# UFC-PCB.net
KiCad netlist of a schematic drawn in Altium Designer
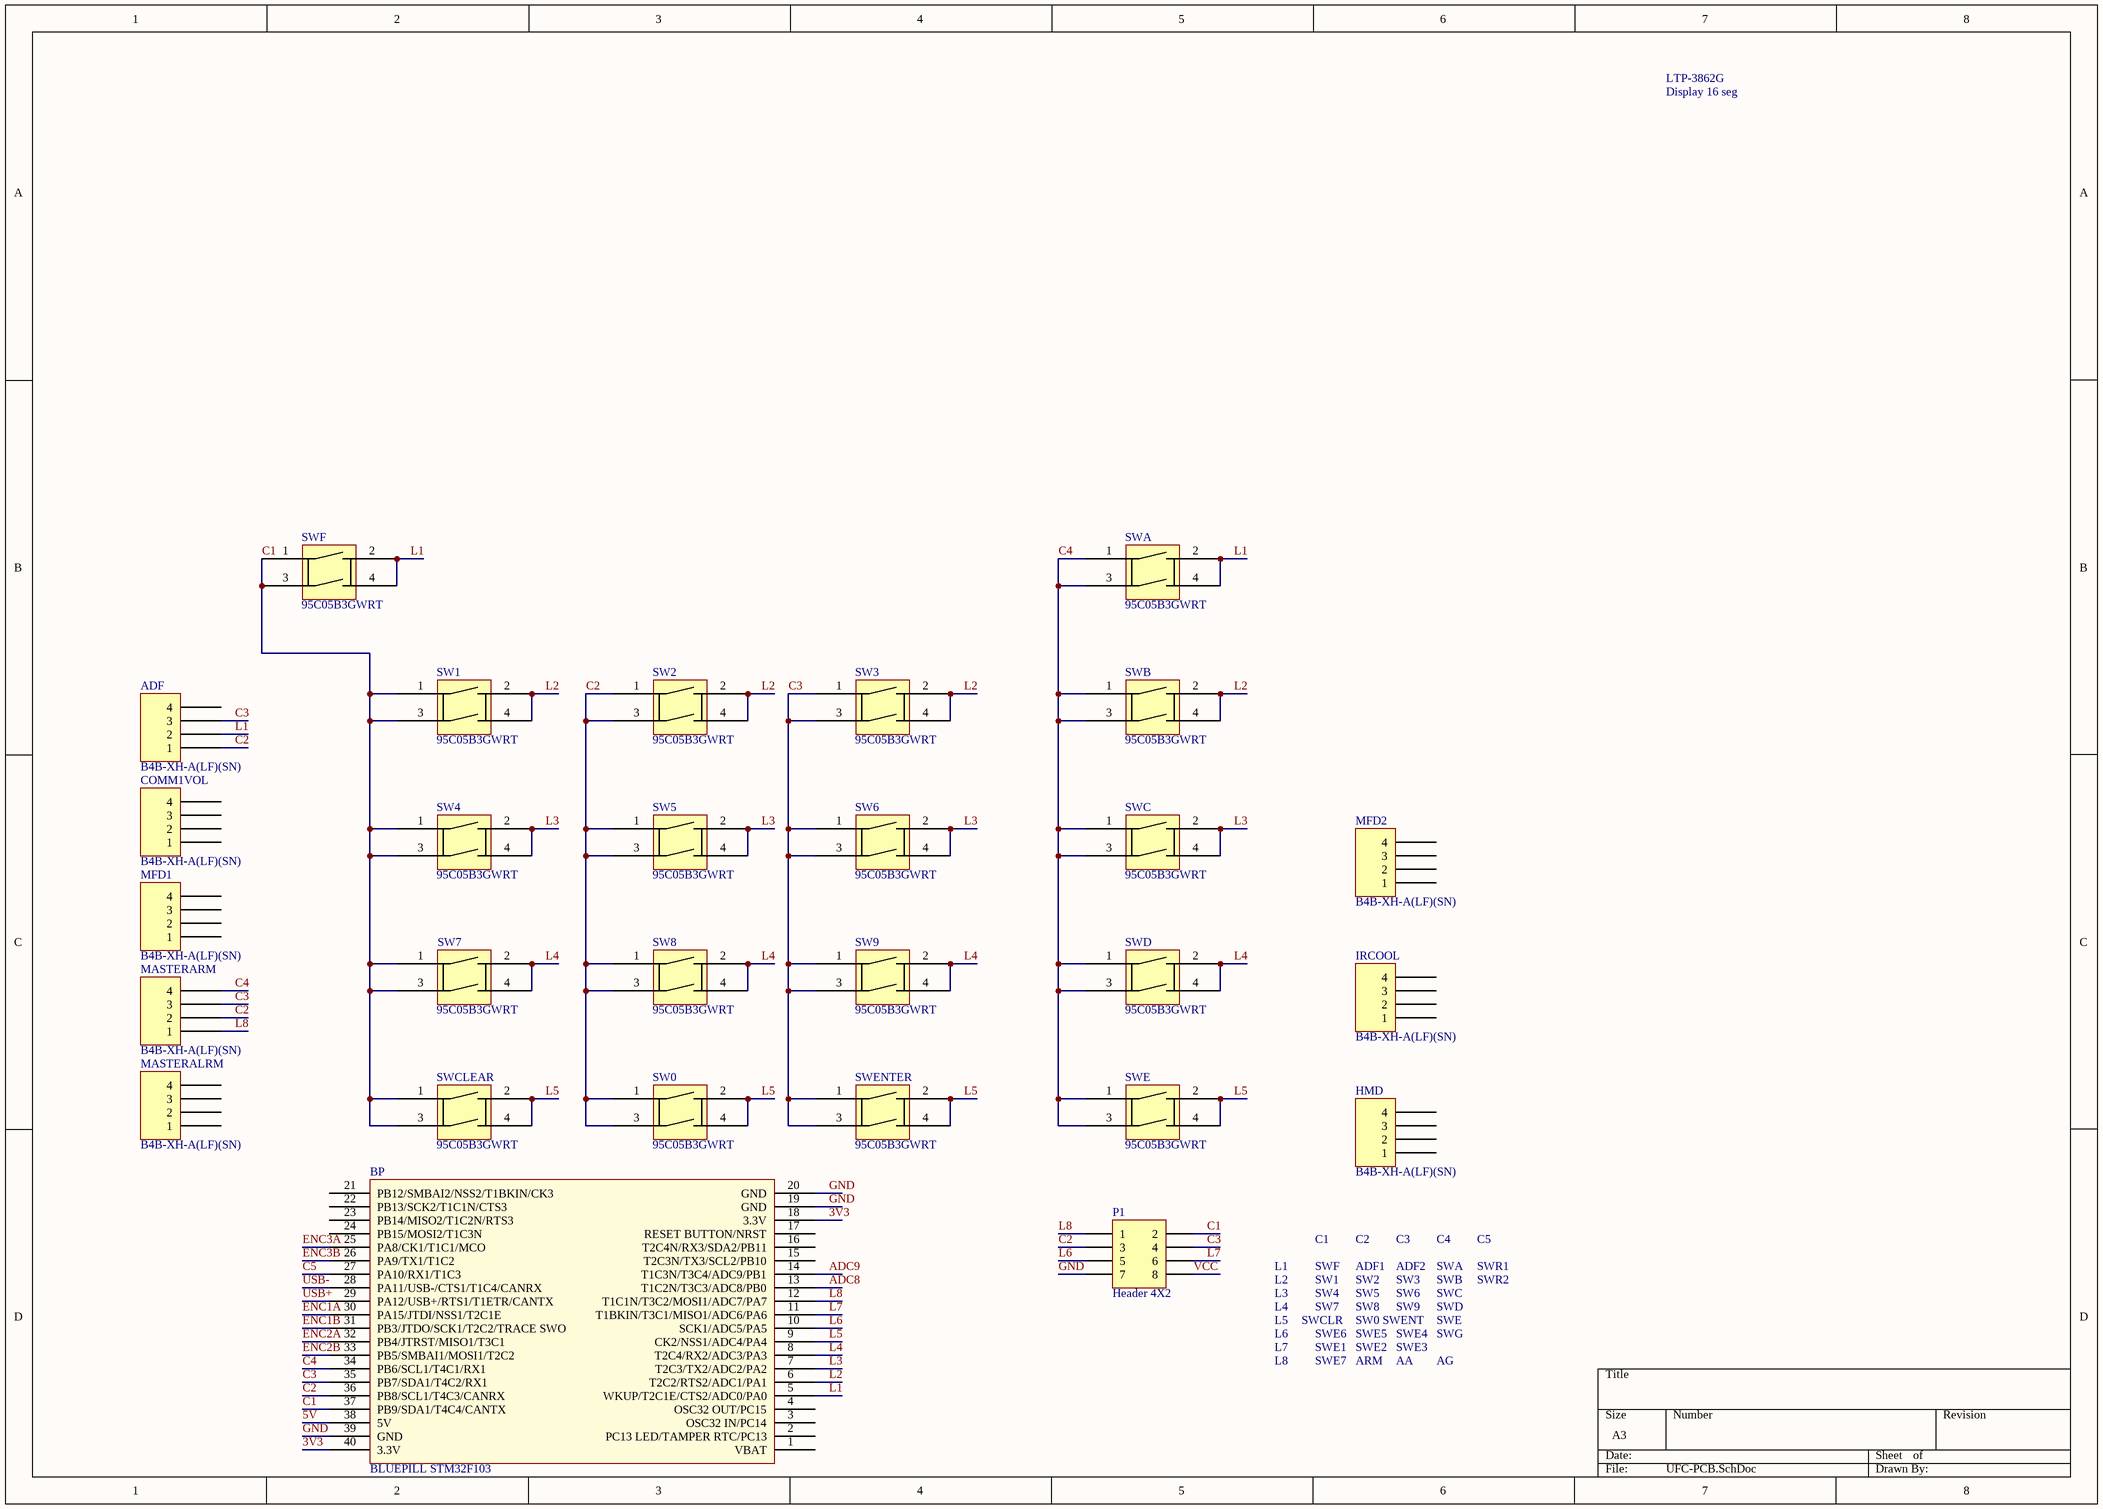
[diagram p0: UFC-PCB.SchDoc]

(export (version "E")
  (design (tool "Eeschema 10.0.6"))
  (components
    (comp (ref "ADF")
      (value "B4B-XH-A(LF)(SN)")
      (footprint "New footprint 1")
      (libsource (lib "IMBEL") (part "4POS CON"))
    )
    (comp (ref "BP")
      (value "BLUEPILL STM32F103")
      (footprint "BLUEPILL-PCB")
      (description "STM32 Blue Pill Development Module")
      (libsource (lib "IMBEL") (part "BLUEPILL-SCH"))
    )
    (comp (ref "COMM1VOL")
      (value "B4B-XH-A(LF)(SN)")
      (footprint "New footprint 1")
      (libsource (lib "IMBEL") (part "4POS CON"))
    )
    (comp (ref "HMD")
      (value "B4B-XH-A(LF)(SN)")
      (footprint "New footprint 1")
      (libsource (lib "IMBEL") (part "4POS CON"))
    )
    (comp (ref "IRCOOL")
      (value "B4B-XH-A(LF)(SN)")
      (footprint "New footprint 1")
      (libsource (lib "IMBEL") (part "4POS CON"))
    )
    (comp (ref "MASTERALRM")
      (value "B4B-XH-A(LF)(SN)")
      (footprint "New footprint 1")
      (libsource (lib "IMBEL") (part "4POS CON"))
    )
    (comp (ref "MASTERARM")
      (value "B4B-XH-A(LF)(SN)")
      (footprint "New footprint 1")
      (libsource (lib "IMBEL") (part "4POS CON"))
    )
    (comp (ref "MFD1")
      (value "B4B-XH-A(LF)(SN)")
      (footprint "New footprint 1")
      (libsource (lib "IMBEL") (part "4POS CON"))
    )
    (comp (ref "MFD2")
      (value "B4B-XH-A(LF)(SN)")
      (footprint "New footprint 1")
      (libsource (lib "IMBEL") (part "4POS CON"))
    )
    (comp (ref "P1")
      (value "Header 4X2")
      (footprint "HDR2X4")
      (description "Header, 4-Pin, Dual row")
      (fields (field (name "PUBLISHER") "Altium Limited"))
      (libsource (lib "Miscellaneous Connectors") (part "Header 4X2"))
    )
    (comp (ref "SW0")
      (value "95C05B3GWRT")
      (footprint "TACTILE-SWITCH-4P")
      (description "SWITCH TACTILE SPST-NO 0.05A 12V")
      (libsource (lib "IMBEL") (part "SWITCH-4P"))
    )
    (comp (ref "SW1")
      (value "95C05B3GWRT")
      (footprint "TACTILE-SWITCH-4P")
      (description "SWITCH TACTILE SPST-NO 0.05A 12V")
      (libsource (lib "IMBEL") (part "SWITCH-4P"))
    )
    (comp (ref "SW2")
      (value "95C05B3GWRT")
      (footprint "TACTILE-SWITCH-4P")
      (description "SWITCH TACTILE SPST-NO 0.05A 12V")
      (libsource (lib "IMBEL") (part "SWITCH-4P"))
    )
    (comp (ref "SW3")
      (value "95C05B3GWRT")
      (footprint "TACTILE-SWITCH-4P")
      (description "SWITCH TACTILE SPST-NO 0.05A 12V")
      (libsource (lib "IMBEL") (part "SWITCH-4P"))
    )
    (comp (ref "SW4")
      (value "95C05B3GWRT")
      (footprint "TACTILE-SWITCH-4P")
      (description "SWITCH TACTILE SPST-NO 0.05A 12V")
      (libsource (lib "IMBEL") (part "SWITCH-4P"))
    )
    (comp (ref "SW5")
      (value "95C05B3GWRT")
      (footprint "TACTILE-SWITCH-4P")
      (description "SWITCH TACTILE SPST-NO 0.05A 12V")
      (libsource (lib "IMBEL") (part "SWITCH-4P"))
    )
    (comp (ref "SW6")
      (value "95C05B3GWRT")
      (footprint "TACTILE-SWITCH-4P")
      (description "SWITCH TACTILE SPST-NO 0.05A 12V")
      (libsource (lib "IMBEL") (part "SWITCH-4P"))
    )
    (comp (ref "SW7")
      (value "95C05B3GWRT")
      (footprint "TACTILE-SWITCH-4P")
      (description "SWITCH TACTILE SPST-NO 0.05A 12V")
      (libsource (lib "IMBEL") (part "SWITCH-4P"))
    )
    (comp (ref "SW8")
      (value "95C05B3GWRT")
      (footprint "TACTILE-SWITCH-4P")
      (description "SWITCH TACTILE SPST-NO 0.05A 12V")
      (libsource (lib "IMBEL") (part "SWITCH-4P"))
    )
    (comp (ref "SW9")
      (value "95C05B3GWRT")
      (footprint "TACTILE-SWITCH-4P")
      (description "SWITCH TACTILE SPST-NO 0.05A 12V")
      (libsource (lib "IMBEL") (part "SWITCH-4P"))
    )
    (comp (ref "SWA")
      (value "95C05B3GWRT")
      (footprint "TACTILE-SWITCH-4P")
      (description "SWITCH TACTILE SPST-NO 0.05A 12V")
      (libsource (lib "IMBEL") (part "SWITCH-4P"))
    )
    (comp (ref "SWB")
      (value "95C05B3GWRT")
      (footprint "TACTILE-SWITCH-4P")
      (description "SWITCH TACTILE SPST-NO 0.05A 12V")
      (libsource (lib "IMBEL") (part "SWITCH-4P"))
    )
    (comp (ref "SWC")
      (value "95C05B3GWRT")
      (footprint "TACTILE-SWITCH-4P")
      (description "SWITCH TACTILE SPST-NO 0.05A 12V")
      (libsource (lib "IMBEL") (part "SWITCH-4P"))
    )
    (comp (ref "SWCLEAR")
      (value "95C05B3GWRT")
      (footprint "TACTILE-SWITCH-4P")
      (description "SWITCH TACTILE SPST-NO 0.05A 12V")
      (libsource (lib "IMBEL") (part "SWITCH-4P"))
    )
    (comp (ref "SWD")
      (value "95C05B3GWRT")
      (footprint "TACTILE-SWITCH-4P")
      (description "SWITCH TACTILE SPST-NO 0.05A 12V")
      (libsource (lib "IMBEL") (part "SWITCH-4P"))
    )
    (comp (ref "SWE")
      (value "95C05B3GWRT")
      (footprint "TACTILE-SWITCH-4P")
      (description "SWITCH TACTILE SPST-NO 0.05A 12V")
      (libsource (lib "IMBEL") (part "SWITCH-4P"))
    )
    (comp (ref "SWENTER")
      (value "95C05B3GWRT")
      (footprint "TACTILE-SWITCH-4P")
      (description "SWITCH TACTILE SPST-NO 0.05A 12V")
      (libsource (lib "IMBEL") (part "SWITCH-4P"))
    )
    (comp (ref "SWF")
      (value "95C05B3GWRT")
      (footprint "TACTILE-SWITCH-4P")
      (description "SWITCH TACTILE SPST-NO 0.05A 12V")
      (libsource (lib "IMBEL") (part "SWITCH-4P"))
    )
  )
  (nets
    (net (code "1") (name "/3V3") (class "Default")
      (node (ref "BP") (pin "18") (pinfunction "3.3V_18") (pintype "passive"))
      (node (ref "BP") (pin "40") (pinfunction "3.3V_40") (pintype "passive"))
    )
    (net (code "2") (name "/5V") (class "Default")
      (node (ref "BP") (pin "38") (pinfunction "5V_38") (pintype "passive"))
    )
    (net (code "3") (name "/ADC8") (class "Default")
      (node (ref "BP") (pin "13") (pinfunction "T1C2N/T3C3/ADC8/PB0_13") (pintype "passive"))
    )
    (net (code "4") (name "/ADC9") (class "Default")
      (node (ref "BP") (pin "14") (pinfunction "T1C3N/T3C4/ADC9/PB1_14") (pintype "passive"))
    )
    (net (code "5") (name "/C1") (class "Default")
      (node (ref "BP") (pin "37") (pinfunction "PB9/SDA1/T4C4/CANTX_37") (pintype "passive"))
      (node (ref "P1") (pin "2") (pinfunction "2_2") (pintype "passive"))
      (node (ref "SW1") (pin "1") (pinfunction "1_1") (pintype "passive"))
      (node (ref "SW1") (pin "3") (pinfunction "3_3") (pintype "passive"))
      (node (ref "SW4") (pin "1") (pinfunction "1_1") (pintype "passive"))
      (node (ref "SW4") (pin "3") (pinfunction "3_3") (pintype "passive"))
      (node (ref "SW7") (pin "1") (pinfunction "1_1") (pintype "passive"))
      (node (ref "SW7") (pin "3") (pinfunction "3_3") (pintype "passive"))
      (node (ref "SWCLEAR") (pin "1") (pinfunction "1_1") (pintype "passive"))
      (node (ref "SWCLEAR") (pin "3") (pinfunction "3_3") (pintype "passive"))
      (node (ref "SWF") (pin "1") (pinfunction "1_1") (pintype "passive"))
      (node (ref "SWF") (pin "3") (pinfunction "3_3") (pintype "passive"))
    )
    (net (code "6") (name "/C2") (class "Default")
      (node (ref "ADF") (pin "1") (pinfunction "1_1") (pintype "open_collector"))
      (node (ref "BP") (pin "36") (pinfunction "PB8/SCL1/T4C3/CANRX_36") (pintype "passive"))
      (node (ref "MASTERARM") (pin "2") (pinfunction "2_2") (pintype "open_collector"))
      (node (ref "P1") (pin "3") (pinfunction "3_3") (pintype "passive"))
      (node (ref "SW0") (pin "1") (pinfunction "1_1") (pintype "passive"))
      (node (ref "SW0") (pin "3") (pinfunction "3_3") (pintype "passive"))
      (node (ref "SW2") (pin "1") (pinfunction "1_1") (pintype "passive"))
      (node (ref "SW2") (pin "3") (pinfunction "3_3") (pintype "passive"))
      (node (ref "SW5") (pin "1") (pinfunction "1_1") (pintype "passive"))
      (node (ref "SW5") (pin "3") (pinfunction "3_3") (pintype "passive"))
      (node (ref "SW8") (pin "1") (pinfunction "1_1") (pintype "passive"))
      (node (ref "SW8") (pin "3") (pinfunction "3_3") (pintype "passive"))
    )
    (net (code "7") (name "/C3") (class "Default")
      (node (ref "ADF") (pin "3") (pinfunction "3_3") (pintype "open_collector"))
      (node (ref "BP") (pin "35") (pinfunction "PB7/SDA1/T4C2/RX1_35") (pintype "passive"))
      (node (ref "MASTERARM") (pin "3") (pinfunction "3_3") (pintype "open_collector"))
      (node (ref "P1") (pin "4") (pinfunction "4_4") (pintype "passive"))
      (node (ref "SW3") (pin "1") (pinfunction "1_1") (pintype "passive"))
      (node (ref "SW3") (pin "3") (pinfunction "3_3") (pintype "passive"))
      (node (ref "SW6") (pin "1") (pinfunction "1_1") (pintype "passive"))
      (node (ref "SW6") (pin "3") (pinfunction "3_3") (pintype "passive"))
      (node (ref "SW9") (pin "1") (pinfunction "1_1") (pintype "passive"))
      (node (ref "SW9") (pin "3") (pinfunction "3_3") (pintype "passive"))
      (node (ref "SWENTER") (pin "1") (pinfunction "1_1") (pintype "passive"))
      (node (ref "SWENTER") (pin "3") (pinfunction "3_3") (pintype "passive"))
    )
    (net (code "8") (name "/C4") (class "Default")
      (node (ref "BP") (pin "34") (pinfunction "PB6/SCL1/T4C1/RX1_34") (pintype "passive"))
      (node (ref "MASTERARM") (pin "4") (pinfunction "4_4") (pintype "open_collector"))
      (node (ref "SWA") (pin "1") (pinfunction "1_1") (pintype "passive"))
      (node (ref "SWA") (pin "3") (pinfunction "3_3") (pintype "passive"))
      (node (ref "SWB") (pin "1") (pinfunction "1_1") (pintype "passive"))
      (node (ref "SWB") (pin "3") (pinfunction "3_3") (pintype "passive"))
      (node (ref "SWC") (pin "1") (pinfunction "1_1") (pintype "passive"))
      (node (ref "SWC") (pin "3") (pinfunction "3_3") (pintype "passive"))
      (node (ref "SWD") (pin "1") (pinfunction "1_1") (pintype "passive"))
      (node (ref "SWD") (pin "3") (pinfunction "3_3") (pintype "passive"))
      (node (ref "SWE") (pin "1") (pinfunction "1_1") (pintype "passive"))
      (node (ref "SWE") (pin "3") (pinfunction "3_3") (pintype "passive"))
    )
    (net (code "9") (name "/C5") (class "Default")
      (node (ref "BP") (pin "27") (pinfunction "PA10/RX1/T1C3_27") (pintype "passive"))
    )
    (net (code "10") (name "/ENC1A") (class "Default")
      (node (ref "BP") (pin "30") (pinfunction "PA15/JTDI/NSS1/T2C1E_30") (pintype "passive"))
    )
    (net (code "11") (name "/ENC1B") (class "Default")
      (node (ref "BP") (pin "31") (pinfunction "PB3/JTDO/SCK1/T2C2/TRACE_SWO_31") (pintype "passive"))
    )
    (net (code "12") (name "/ENC2A") (class "Default")
      (node (ref "BP") (pin "32") (pinfunction "PB4/JTRST/MISO1/T3C1_32") (pintype "passive"))
    )
    (net (code "13") (name "/ENC2B") (class "Default")
      (node (ref "BP") (pin "33") (pinfunction "PB5/SMBAI1/MOSI1/T2C2_33") (pintype "passive"))
    )
    (net (code "14") (name "/ENC3A") (class "Default")
      (node (ref "BP") (pin "25") (pinfunction "PA8/CK1/T1C1/MCO_25") (pintype "passive"))
    )
    (net (code "15") (name "/ENC3B") (class "Default")
      (node (ref "BP") (pin "26") (pinfunction "PA9/TX1/T1C2_26") (pintype "passive"))
    )
    (net (code "16") (name "/GND") (class "Default")
      (node (ref "BP") (pin "19") (pinfunction "GND_19") (pintype "passive"))
      (node (ref "BP") (pin "20") (pinfunction "GND_20") (pintype "passive"))
      (node (ref "BP") (pin "39") (pinfunction "GND_39") (pintype "passive"))
      (node (ref "P1") (pin "7") (pinfunction "7_7") (pintype "passive"))
    )
    (net (code "17") (name "/L1") (class "Default")
      (node (ref "ADF") (pin "2") (pinfunction "2_2") (pintype "open_collector"))
      (node (ref "BP") (pin "5") (pinfunction "WKUP/T2C1E/CTS2/ADC0/PA0_5") (pintype "passive"))
      (node (ref "SWA") (pin "2") (pinfunction "2_2") (pintype "passive"))
      (node (ref "SWA") (pin "4") (pinfunction "4_4") (pintype "passive"))
      (node (ref "SWF") (pin "2") (pinfunction "2_2") (pintype "passive"))
      (node (ref "SWF") (pin "4") (pinfunction "4_4") (pintype "passive"))
    )
    (net (code "18") (name "/L2") (class "Default")
      (node (ref "BP") (pin "6") (pinfunction "T2C2/RTS2/ADC1/PA1_6") (pintype "passive"))
      (node (ref "SW1") (pin "2") (pinfunction "2_2") (pintype "passive"))
      (node (ref "SW1") (pin "4") (pinfunction "4_4") (pintype "passive"))
      (node (ref "SW2") (pin "2") (pinfunction "2_2") (pintype "passive"))
      (node (ref "SW2") (pin "4") (pinfunction "4_4") (pintype "passive"))
      (node (ref "SW3") (pin "2") (pinfunction "2_2") (pintype "passive"))
      (node (ref "SW3") (pin "4") (pinfunction "4_4") (pintype "passive"))
      (node (ref "SWB") (pin "2") (pinfunction "2_2") (pintype "passive"))
      (node (ref "SWB") (pin "4") (pinfunction "4_4") (pintype "passive"))
    )
    (net (code "19") (name "/L3") (class "Default")
      (node (ref "BP") (pin "7") (pinfunction "T2C3/TX2/ADC2/PA2_7") (pintype "passive"))
      (node (ref "SW4") (pin "2") (pinfunction "2_2") (pintype "passive"))
      (node (ref "SW4") (pin "4") (pinfunction "4_4") (pintype "passive"))
      (node (ref "SW5") (pin "2") (pinfunction "2_2") (pintype "passive"))
      (node (ref "SW5") (pin "4") (pinfunction "4_4") (pintype "passive"))
      (node (ref "SW6") (pin "2") (pinfunction "2_2") (pintype "passive"))
      (node (ref "SW6") (pin "4") (pinfunction "4_4") (pintype "passive"))
      (node (ref "SWC") (pin "2") (pinfunction "2_2") (pintype "passive"))
      (node (ref "SWC") (pin "4") (pinfunction "4_4") (pintype "passive"))
    )
    (net (code "20") (name "/L4") (class "Default")
      (node (ref "BP") (pin "8") (pinfunction "T2C4/RX2/ADC3/PA3_8") (pintype "passive"))
      (node (ref "SW7") (pin "2") (pinfunction "2_2") (pintype "passive"))
      (node (ref "SW7") (pin "4") (pinfunction "4_4") (pintype "passive"))
      (node (ref "SW8") (pin "2") (pinfunction "2_2") (pintype "passive"))
      (node (ref "SW8") (pin "4") (pinfunction "4_4") (pintype "passive"))
      (node (ref "SW9") (pin "2") (pinfunction "2_2") (pintype "passive"))
      (node (ref "SW9") (pin "4") (pinfunction "4_4") (pintype "passive"))
      (node (ref "SWD") (pin "2") (pinfunction "2_2") (pintype "passive"))
      (node (ref "SWD") (pin "4") (pinfunction "4_4") (pintype "passive"))
    )
    (net (code "21") (name "/L5") (class "Default")
      (node (ref "BP") (pin "9") (pinfunction "CK2/NSS1/ADC4/PA4_9") (pintype "passive"))
      (node (ref "SW0") (pin "2") (pinfunction "2_2") (pintype "passive"))
      (node (ref "SW0") (pin "4") (pinfunction "4_4") (pintype "passive"))
      (node (ref "SWCLEAR") (pin "2") (pinfunction "2_2") (pintype "passive"))
      (node (ref "SWCLEAR") (pin "4") (pinfunction "4_4") (pintype "passive"))
      (node (ref "SWE") (pin "2") (pinfunction "2_2") (pintype "passive"))
      (node (ref "SWE") (pin "4") (pinfunction "4_4") (pintype "passive"))
      (node (ref "SWENTER") (pin "2") (pinfunction "2_2") (pintype "passive"))
      (node (ref "SWENTER") (pin "4") (pinfunction "4_4") (pintype "passive"))
    )
    (net (code "22") (name "/L6") (class "Default")
      (node (ref "BP") (pin "10") (pinfunction "SCK1/ADC5/PA5_10") (pintype "passive"))
      (node (ref "P1") (pin "5") (pinfunction "5_5") (pintype "passive"))
    )
    (net (code "23") (name "/L7") (class "Default")
      (node (ref "BP") (pin "11") (pinfunction "T1BKIN/T3C1/MISO1/ADC6/PA6_11") (pintype "passive"))
      (node (ref "P1") (pin "6") (pinfunction "6_6") (pintype "passive"))
    )
    (net (code "24") (name "/L8") (class "Default")
      (node (ref "BP") (pin "12") (pinfunction "T1C1N/T3C2/MOSI1/ADC7/PA7_12") (pintype "passive"))
      (node (ref "MASTERARM") (pin "1") (pinfunction "1_1") (pintype "open_collector"))
      (node (ref "P1") (pin "1") (pinfunction "1_1") (pintype "passive"))
    )
    (net (code "25") (name "/USB+") (class "Default")
      (node (ref "BP") (pin "29") (pinfunction "PA12/USB+/RTS1/T1ETR/CANTX_29") (pintype "passive"))
    )
    (net (code "26") (name "/USB-") (class "Default")
      (node (ref "BP") (pin "28") (pinfunction "PA11/USB-/CTS1/T1C4/CANRX_28") (pintype "passive"))
    )
    (net (code "27") (name "/VCC") (class "Default")
      (node (ref "P1") (pin "8") (pinfunction "8_8") (pintype "passive"))
    )
    (net (code "28") (name "unconnected-(ADF-Pad4)") (class "Default")
      (node (ref "ADF") (pin "4") (pinfunction "4_4") (pintype "open_collector"))
    )
    (net (code "29") (name "unconnected-(BP-OSC32_IN{slash}PC14-Pad3)") (class "Default")
      (node (ref "BP") (pin "3") (pinfunction "OSC32_IN/PC14_3") (pintype "passive"))
    )
    (net (code "30") (name "unconnected-(BP-OSC32_OUT{slash}PC15-Pad4)") (class "Default")
      (node (ref "BP") (pin "4") (pinfunction "OSC32_OUT/PC15_4") (pintype "passive"))
    )
    (net (code "31") (name "unconnected-(BP-PB12{slash}SMBAI2{slash}NSS2{slash}T1BKIN{slash}CK3-Pad21)") (class "Default")
      (node (ref "BP") (pin "21") (pinfunction "PB12/SMBAI2/NSS2/T1BKIN/CK3_21") (pintype "passive"))
    )
    (net (code "32") (name "unconnected-(BP-PB13{slash}SCK2{slash}T1C1N{slash}CTS3-Pad22)") (class "Default")
      (node (ref "BP") (pin "22") (pinfunction "PB13/SCK2/T1C1N/CTS3_22") (pintype "passive"))
    )
    (net (code "33") (name "unconnected-(BP-PB14{slash}MISO2{slash}T1C2N{slash}RTS3-Pad23)") (class "Default")
      (node (ref "BP") (pin "23") (pinfunction "PB14/MISO2/T1C2N/RTS3_23") (pintype "passive"))
    )
    (net (code "34") (name "unconnected-(BP-PB15{slash}MOSI2{slash}T1C3N-Pad24)") (class "Default")
      (node (ref "BP") (pin "24") (pinfunction "PB15/MOSI2/T1C3N_24") (pintype "passive"))
    )
    (net (code "35") (name "unconnected-(BP-PC13_LED{slash}TAMPER_RTC{slash}PC13-Pad2)") (class "Default")
      (node (ref "BP") (pin "2") (pinfunction "PC13_LED/TAMPER_RTC/PC13_2") (pintype "passive"))
    )
    (net (code "36") (name "unconnected-(BP-RESET_BUTTON{slash}NRST-Pad17)") (class "Default")
      (node (ref "BP") (pin "17") (pinfunction "RESET_BUTTON/NRST_17") (pintype "passive"))
    )
    (net (code "37") (name "unconnected-(BP-T2C3N{slash}TX3{slash}SCL2{slash}PB10-Pad15)") (class "Default")
      (node (ref "BP") (pin "15") (pinfunction "T2C3N/TX3/SCL2/PB10_15") (pintype "passive"))
    )
    (net (code "38") (name "unconnected-(BP-T2C4N{slash}RX3{slash}SDA2{slash}PB11-Pad16)") (class "Default")
      (node (ref "BP") (pin "16") (pinfunction "T2C4N/RX3/SDA2/PB11_16") (pintype "passive"))
    )
    (net (code "39") (name "unconnected-(BP-VBAT-Pad1)") (class "Default")
      (node (ref "BP") (pin "1") (pinfunction "VBAT_1") (pintype "passive"))
    )
    (net (code "40") (name "unconnected-(COMM1VOL-Pad1)") (class "Default")
      (node (ref "COMM1VOL") (pin "1") (pinfunction "1_1") (pintype "open_collector"))
    )
    (net (code "41") (name "unconnected-(COMM1VOL-Pad2)") (class "Default")
      (node (ref "COMM1VOL") (pin "2") (pinfunction "2_2") (pintype "open_collector"))
    )
    (net (code "42") (name "unconnected-(COMM1VOL-Pad3)") (class "Default")
      (node (ref "COMM1VOL") (pin "3") (pinfunction "3_3") (pintype "open_collector"))
    )
    (net (code "43") (name "unconnected-(COMM1VOL-Pad4)") (class "Default")
      (node (ref "COMM1VOL") (pin "4") (pinfunction "4_4") (pintype "open_collector"))
    )
    (net (code "44") (name "unconnected-(HMD-Pad1)") (class "Default")
      (node (ref "HMD") (pin "1") (pinfunction "1_1") (pintype "open_collector"))
    )
    (net (code "45") (name "unconnected-(HMD-Pad2)") (class "Default")
      (node (ref "HMD") (pin "2") (pinfunction "2_2") (pintype "open_collector"))
    )
    (net (code "46") (name "unconnected-(HMD-Pad3)") (class "Default")
      (node (ref "HMD") (pin "3") (pinfunction "3_3") (pintype "open_collector"))
    )
    (net (code "47") (name "unconnected-(HMD-Pad4)") (class "Default")
      (node (ref "HMD") (pin "4") (pinfunction "4_4") (pintype "open_collector"))
    )
    (net (code "48") (name "unconnected-(IRCOOL-Pad1)") (class "Default")
      (node (ref "IRCOOL") (pin "1") (pinfunction "1_1") (pintype "open_collector"))
    )
    (net (code "49") (name "unconnected-(IRCOOL-Pad2)") (class "Default")
      (node (ref "IRCOOL") (pin "2") (pinfunction "2_2") (pintype "open_collector"))
    )
    (net (code "50") (name "unconnected-(IRCOOL-Pad3)") (class "Default")
      (node (ref "IRCOOL") (pin "3") (pinfunction "3_3") (pintype "open_collector"))
    )
    (net (code "51") (name "unconnected-(IRCOOL-Pad4)") (class "Default")
      (node (ref "IRCOOL") (pin "4") (pinfunction "4_4") (pintype "open_collector"))
    )
    (net (code "52") (name "unconnected-(MASTERALRM-Pad1)") (class "Default")
      (node (ref "MASTERALRM") (pin "1") (pinfunction "1_1") (pintype "open_collector"))
    )
    (net (code "53") (name "unconnected-(MASTERALRM-Pad2)") (class "Default")
      (node (ref "MASTERALRM") (pin "2") (pinfunction "2_2") (pintype "open_collector"))
    )
    (net (code "54") (name "unconnected-(MASTERALRM-Pad3)") (class "Default")
      (node (ref "MASTERALRM") (pin "3") (pinfunction "3_3") (pintype "open_collector"))
    )
    (net (code "55") (name "unconnected-(MASTERALRM-Pad4)") (class "Default")
      (node (ref "MASTERALRM") (pin "4") (pinfunction "4_4") (pintype "open_collector"))
    )
    (net (code "56") (name "unconnected-(MFD1-Pad1)") (class "Default")
      (node (ref "MFD1") (pin "1") (pinfunction "1_1") (pintype "open_collector"))
    )
    (net (code "57") (name "unconnected-(MFD1-Pad2)") (class "Default")
      (node (ref "MFD1") (pin "2") (pinfunction "2_2") (pintype "open_collector"))
    )
    (net (code "58") (name "unconnected-(MFD1-Pad3)") (class "Default")
      (node (ref "MFD1") (pin "3") (pinfunction "3_3") (pintype "open_collector"))
    )
    (net (code "59") (name "unconnected-(MFD1-Pad4)") (class "Default")
      (node (ref "MFD1") (pin "4") (pinfunction "4_4") (pintype "open_collector"))
    )
    (net (code "60") (name "unconnected-(MFD2-Pad1)") (class "Default")
      (node (ref "MFD2") (pin "1") (pinfunction "1_1") (pintype "open_collector"))
    )
    (net (code "61") (name "unconnected-(MFD2-Pad2)") (class "Default")
      (node (ref "MFD2") (pin "2") (pinfunction "2_2") (pintype "open_collector"))
    )
    (net (code "62") (name "unconnected-(MFD2-Pad3)") (class "Default")
      (node (ref "MFD2") (pin "3") (pinfunction "3_3") (pintype "open_collector"))
    )
    (net (code "63") (name "unconnected-(MFD2-Pad4)") (class "Default")
      (node (ref "MFD2") (pin "4") (pinfunction "4_4") (pintype "open_collector"))
    )
  )
)
